# EthernetBridge.net
KiCad netlist of a schematic drawn in EAGLE
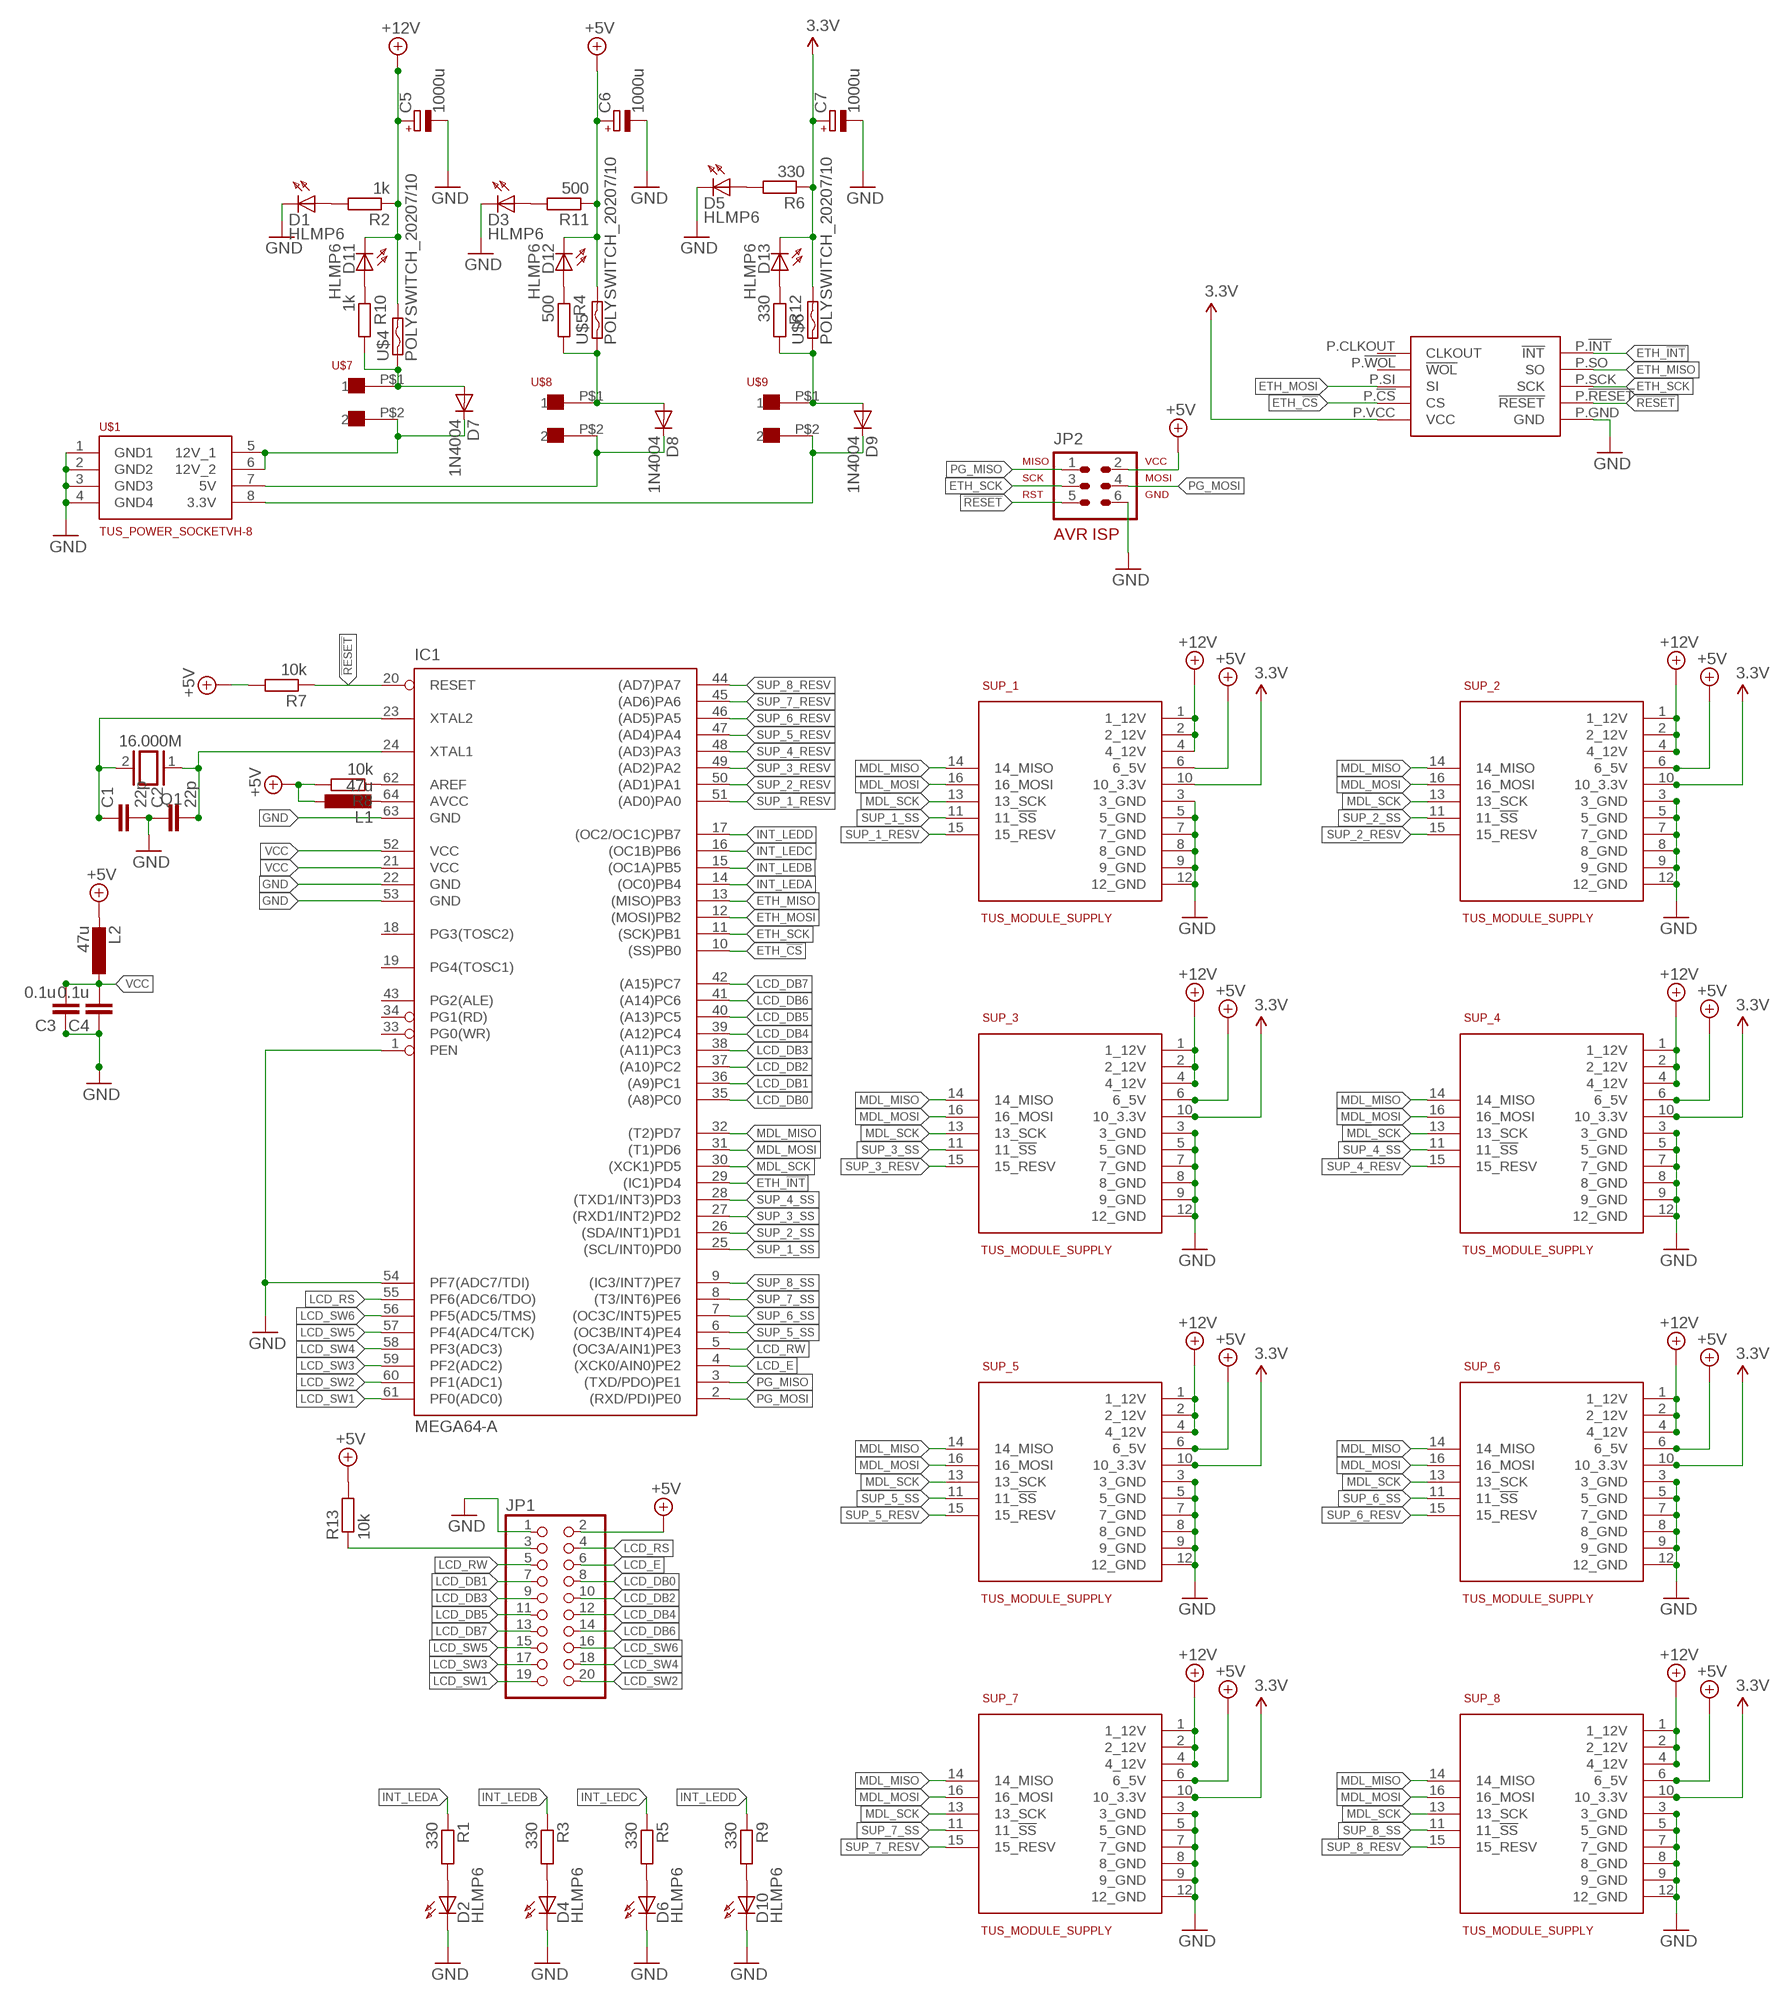
[diagram p0: schematic, sheet 1]

(export (version "E")
  (design (tool "Eeschema 10.0.6"))
  (components
    (comp (ref "C1")
      (value "22p")
      (footprint "eagle-import:C2.5-3")
      (libsource (lib "eagle-import") (part "C2,5-3"))
    )
    (comp (ref "C2")
      (value "22p")
      (footprint "eagle-import:C2.5-3")
      (libsource (lib "eagle-import") (part "C2,5-3"))
    )
    (comp (ref "C3")
      (value "0.1u")
      (footprint "eagle-import:C2.5-3")
      (libsource (lib "eagle-import") (part "C2,5-3"))
    )
    (comp (ref "C4")
      (value "0.1u")
      (footprint "eagle-import:C2.5-3")
      (libsource (lib "eagle-import") (part "C2,5-3"))
    )
    (comp (ref "C5")
      (value "1000u")
      (footprint "eagle-import:E5-10,5")
      (libsource (lib "eagle-import") (part "CPOL-EUE5-10.5"))
    )
    (comp (ref "C6")
      (value "1000u")
      (footprint "eagle-import:E5-10,5")
      (libsource (lib "eagle-import") (part "CPOL-EUE5-10.5"))
    )
    (comp (ref "C7")
      (value "1000u")
      (footprint "eagle-import:E5-10,5")
      (libsource (lib "eagle-import") (part "CPOL-EUE5-10.5"))
    )
    (comp (ref "D1")
      (value "HLMP6")
      (footprint "eagle-import:HLMP6")
      (fields (field (name "MF") "AGILENT TECHNOLOGIES") (field (name "MPN") "HLMP-6500"))
      (libsource (lib "eagle-import") (part "HLMP6"))
    )
    (comp (ref "D2")
      (value "HLMP6")
      (footprint "eagle-import:HLMP6")
      (fields (field (name "MF") "AGILENT TECHNOLOGIES") (field (name "MPN") "HLMP-6500"))
      (libsource (lib "eagle-import") (part "HLMP6"))
    )
    (comp (ref "D3")
      (value "HLMP6")
      (footprint "eagle-import:HLMP6")
      (fields (field (name "MF") "AGILENT TECHNOLOGIES") (field (name "MPN") "HLMP-6500"))
      (libsource (lib "eagle-import") (part "HLMP6"))
    )
    (comp (ref "D4")
      (value "HLMP6")
      (footprint "eagle-import:HLMP6")
      (fields (field (name "MF") "AGILENT TECHNOLOGIES") (field (name "MPN") "HLMP-6500"))
      (libsource (lib "eagle-import") (part "HLMP6"))
    )
    (comp (ref "D5")
      (value "HLMP6")
      (footprint "eagle-import:HLMP6")
      (fields (field (name "MF") "AGILENT TECHNOLOGIES") (field (name "MPN") "HLMP-6500"))
      (libsource (lib "eagle-import") (part "HLMP6"))
    )
    (comp (ref "D6")
      (value "HLMP6")
      (footprint "eagle-import:HLMP6")
      (fields (field (name "MF") "AGILENT TECHNOLOGIES") (field (name "MPN") "HLMP-6500"))
      (libsource (lib "eagle-import") (part "HLMP6"))
    )
    (comp (ref "D7")
      (value "1N4004")
      (footprint "eagle-import:DO41-10")
      (libsource (lib "eagle-import") (part "1N4004"))
    )
    (comp (ref "D8")
      (value "1N4004")
      (footprint "eagle-import:DO41-10")
      (libsource (lib "eagle-import") (part "1N4004"))
    )
    (comp (ref "D9")
      (value "1N4004")
      (footprint "eagle-import:DO41-10")
      (libsource (lib "eagle-import") (part "1N4004"))
    )
    (comp (ref "D10")
      (value "HLMP6")
      (footprint "eagle-import:HLMP6")
      (fields (field (name "MF") "AGILENT TECHNOLOGIES") (field (name "MPN") "HLMP-6500"))
      (libsource (lib "eagle-import") (part "HLMP6"))
    )
    (comp (ref "D11")
      (value "HLMP6")
      (footprint "eagle-import:HLMP6")
      (fields (field (name "MF") "AGILENT TECHNOLOGIES") (field (name "MPN") "HLMP-6500"))
      (libsource (lib "eagle-import") (part "HLMP6"))
    )
    (comp (ref "D12")
      (value "HLMP6")
      (footprint "eagle-import:HLMP6")
      (fields (field (name "MF") "AGILENT TECHNOLOGIES") (field (name "MPN") "HLMP-6500"))
      (libsource (lib "eagle-import") (part "HLMP6"))
    )
    (comp (ref "D13")
      (value "HLMP6")
      (footprint "eagle-import:HLMP6")
      (fields (field (name "MF") "AGILENT TECHNOLOGIES") (field (name "MPN") "HLMP-6500"))
      (libsource (lib "eagle-import") (part "HLMP6"))
    )
    (comp (ref "IC1")
      (value "MEGA64-A")
      (footprint "eagle-import:TQFP64")
      (fields (field (name "MPN") "ATMEGA64-16AU"))
      (libsource (lib "eagle-import") (part "MEGA64-A"))
    )
    (comp (ref "JP1")
      (value "PINHD-2X10")
      (footprint "eagle-import:2X10")
      (libsource (lib "eagle-import") (part "PINHD-2X10"))
    )
    (comp (ref "JP2")
      (value "AVR-ISP-6VERT")
      (footprint "eagle-import:AVR-ISP-6")
      (libsource (lib "eagle-import") (part "AVR-ISP-6VERT"))
    )
    (comp (ref "L1")
      (value "47u")
      (footprint "eagle-import:0204_7")
      (libsource (lib "eagle-import") (part "L-EU0204/7"))
    )
    (comp (ref "L2")
      (value "47u")
      (footprint "eagle-import:0204_7")
      (libsource (lib "eagle-import") (part "L-EU0204/7"))
    )
    (comp (ref "Q1")
      (value "16.000M")
      (footprint "eagle-import:QS")
      (libsource (lib "eagle-import") (part "XTAL/S"))
    )
    (comp (ref "R1")
      (value "330")
      (footprint "eagle-import:0204_7")
      (libsource (lib "eagle-import") (part "R-EU_0204/7"))
    )
    (comp (ref "R2")
      (value "1k")
      (footprint "eagle-import:0204_7")
      (libsource (lib "eagle-import") (part "R-EU_0204/7"))
    )
    (comp (ref "R3")
      (value "330")
      (footprint "eagle-import:0204_7")
      (libsource (lib "eagle-import") (part "R-EU_0204/7"))
    )
    (comp (ref "R4")
      (value "500")
      (footprint "eagle-import:0204_7")
      (libsource (lib "eagle-import") (part "R-EU_0204/7"))
    )
    (comp (ref "R5")
      (value "330")
      (footprint "eagle-import:0204_7")
      (libsource (lib "eagle-import") (part "R-EU_0204/7"))
    )
    (comp (ref "R6")
      (value "330")
      (footprint "eagle-import:0204_7")
      (libsource (lib "eagle-import") (part "R-EU_0204/7"))
    )
    (comp (ref "R7")
      (value "10k")
      (footprint "eagle-import:0204_7")
      (libsource (lib "eagle-import") (part "R-EU_0204/7"))
    )
    (comp (ref "R8")
      (value "10k")
      (footprint "eagle-import:0204_7")
      (libsource (lib "eagle-import") (part "R-EU_0204/7"))
    )
    (comp (ref "R9")
      (value "330")
      (footprint "eagle-import:0204_7")
      (libsource (lib "eagle-import") (part "R-EU_0204/7"))
    )
    (comp (ref "R10")
      (value "1k")
      (footprint "eagle-import:0204_7")
      (libsource (lib "eagle-import") (part "R-EU_0204/7"))
    )
    (comp (ref "R11")
      (value "500")
      (footprint "eagle-import:0204_7")
      (libsource (lib "eagle-import") (part "R-EU_0204/7"))
    )
    (comp (ref "R12")
      (value "330")
      (footprint "eagle-import:0204_7")
      (libsource (lib "eagle-import") (part "R-EU_0204/7"))
    )
    (comp (ref "R13")
      (value "10k")
      (footprint "eagle-import:0204_7")
      (libsource (lib "eagle-import") (part "R-EU_0204/7"))
    )
    (comp (ref "SUP_1")
      (value "TUS_MODULE_SUPPLY")
      (footprint "eagle-import:2X08")
      (libsource (lib "eagle-import") (part "TUS_MODULE_SUPPLY"))
    )
    (comp (ref "SUP_2")
      (value "TUS_MODULE_SUPPLY")
      (footprint "eagle-import:2X08")
      (libsource (lib "eagle-import") (part "TUS_MODULE_SUPPLY"))
    )
    (comp (ref "SUP_3")
      (value "TUS_MODULE_SUPPLY")
      (footprint "eagle-import:2X08")
      (libsource (lib "eagle-import") (part "TUS_MODULE_SUPPLY"))
    )
    (comp (ref "SUP_4")
      (value "TUS_MODULE_SUPPLY")
      (footprint "eagle-import:2X08")
      (libsource (lib "eagle-import") (part "TUS_MODULE_SUPPLY"))
    )
    (comp (ref "SUP_5")
      (value "TUS_MODULE_SUPPLY")
      (footprint "eagle-import:2X08")
      (libsource (lib "eagle-import") (part "TUS_MODULE_SUPPLY"))
    )
    (comp (ref "SUP_6")
      (value "TUS_MODULE_SUPPLY")
      (footprint "eagle-import:2X08")
      (libsource (lib "eagle-import") (part "TUS_MODULE_SUPPLY"))
    )
    (comp (ref "SUP_7")
      (value "TUS_MODULE_SUPPLY")
      (footprint "eagle-import:2X08")
      (libsource (lib "eagle-import") (part "TUS_MODULE_SUPPLY"))
    )
    (comp (ref "SUP_8")
      (value "TUS_MODULE_SUPPLY")
      (footprint "eagle-import:2X08")
      (libsource (lib "eagle-import") (part "TUS_MODULE_SUPPLY"))
    )
    (comp (ref "U$1")
      (value "TUS_POWER_SOCKETVH-8")
      (footprint "eagle-import:VH_8")
      (libsource (lib "eagle-import") (part "TUS_POWER_SOCKETVH-8"))
    )
    (comp (ref "U$2")
      (value "AITENDO_ENC28J60")
      (footprint "eagle-import:AITENDO_ENC28J60")
      (libsource (lib "eagle-import") (part "AITENDO_ENC28J60"))
    )
    (comp (ref "U$4")
      (value "POLYSWITCH_20207/10")
      (footprint "eagle-import:0207_10")
      (libsource (lib "eagle-import") (part "POLYSWITCH_20207/10"))
    )
    (comp (ref "U$5")
      (value "POLYSWITCH_20207/10")
      (footprint "eagle-import:0207_10")
      (libsource (lib "eagle-import") (part "POLYSWITCH_20207/10"))
    )
    (comp (ref "U$6")
      (value "POLYSWITCH_20207/10")
      (footprint "eagle-import:0207_10")
      (libsource (lib "eagle-import") (part "POLYSWITCH_20207/10"))
    )
    (comp (ref "U$7")
      (value "VH-2")
      (footprint "eagle-import:VH-2")
      (libsource (lib "eagle-import") (part "VH-2"))
    )
    (comp (ref "U$8")
      (value "VH-2")
      (footprint "eagle-import:VH-2")
      (libsource (lib "eagle-import") (part "VH-2"))
    )
    (comp (ref "U$9")
      (value "VH-2")
      (footprint "eagle-import:VH-2")
      (libsource (lib "eagle-import") (part "VH-2"))
    )
  )
  (nets
    (net (code "1") (name "+5V") (class "Default")
      (node (ref "C6") (pin "+") (pinfunction "+_+") (pintype "passive"))
      (node (ref "D12") (pin "K") (pinfunction "K_K") (pintype "passive"))
      (node (ref "JP1") (pin "2") (pinfunction "2_2") (pintype "passive"))
      (node (ref "JP2") (pin "2") (pinfunction "2_2") (pintype "passive"))
      (node (ref "L1") (pin "1") (pinfunction "1_1") (pintype "passive"))
      (node (ref "L2") (pin "2") (pinfunction "2_2") (pintype "passive"))
      (node (ref "R11") (pin "1") (pinfunction "1_1") (pintype "passive"))
      (node (ref "R13") (pin "2") (pinfunction "2_2") (pintype "passive"))
      (node (ref "R7") (pin "2") (pinfunction "2_2") (pintype "passive"))
      (node (ref "R8") (pin "2") (pinfunction "2_2") (pintype "passive"))
      (node (ref "SUP_1") (pin "6") (pinfunction "6_5V_6") (pintype "bidirectional"))
      (node (ref "SUP_2") (pin "6") (pinfunction "6_5V_6") (pintype "bidirectional"))
      (node (ref "SUP_3") (pin "6") (pinfunction "6_5V_6") (pintype "bidirectional"))
      (node (ref "SUP_4") (pin "6") (pinfunction "6_5V_6") (pintype "bidirectional"))
      (node (ref "SUP_5") (pin "6") (pinfunction "6_5V_6") (pintype "bidirectional"))
      (node (ref "SUP_6") (pin "6") (pinfunction "6_5V_6") (pintype "bidirectional"))
      (node (ref "SUP_7") (pin "6") (pinfunction "6_5V_6") (pintype "bidirectional"))
      (node (ref "SUP_8") (pin "6") (pinfunction "6_5V_6") (pintype "bidirectional"))
      (node (ref "U$5") (pin "2") (pinfunction "2_2") (pintype "passive"))
    )
    (net (code "2") (name "+12V") (class "Default")
      (node (ref "C5") (pin "+") (pinfunction "+_+") (pintype "passive"))
      (node (ref "D11") (pin "K") (pinfunction "K_K") (pintype "passive"))
      (node (ref "R2") (pin "1") (pinfunction "1_1") (pintype "passive"))
      (node (ref "SUP_1") (pin "1") (pinfunction "1_12V_1") (pintype "bidirectional"))
      (node (ref "SUP_1") (pin "2") (pinfunction "2_12V_2") (pintype "bidirectional"))
      (node (ref "SUP_1") (pin "4") (pinfunction "4_12V_4") (pintype "bidirectional"))
      (node (ref "SUP_2") (pin "1") (pinfunction "1_12V_1") (pintype "bidirectional"))
      (node (ref "SUP_2") (pin "2") (pinfunction "2_12V_2") (pintype "bidirectional"))
      (node (ref "SUP_2") (pin "4") (pinfunction "4_12V_4") (pintype "bidirectional"))
      (node (ref "SUP_3") (pin "1") (pinfunction "1_12V_1") (pintype "bidirectional"))
      (node (ref "SUP_3") (pin "2") (pinfunction "2_12V_2") (pintype "bidirectional"))
      (node (ref "SUP_3") (pin "4") (pinfunction "4_12V_4") (pintype "bidirectional"))
      (node (ref "SUP_4") (pin "1") (pinfunction "1_12V_1") (pintype "bidirectional"))
      (node (ref "SUP_4") (pin "2") (pinfunction "2_12V_2") (pintype "bidirectional"))
      (node (ref "SUP_4") (pin "4") (pinfunction "4_12V_4") (pintype "bidirectional"))
      (node (ref "SUP_5") (pin "1") (pinfunction "1_12V_1") (pintype "bidirectional"))
      (node (ref "SUP_5") (pin "2") (pinfunction "2_12V_2") (pintype "bidirectional"))
      (node (ref "SUP_5") (pin "4") (pinfunction "4_12V_4") (pintype "bidirectional"))
      (node (ref "SUP_6") (pin "1") (pinfunction "1_12V_1") (pintype "bidirectional"))
      (node (ref "SUP_6") (pin "2") (pinfunction "2_12V_2") (pintype "bidirectional"))
      (node (ref "SUP_6") (pin "4") (pinfunction "4_12V_4") (pintype "bidirectional"))
      (node (ref "SUP_7") (pin "1") (pinfunction "1_12V_1") (pintype "bidirectional"))
      (node (ref "SUP_7") (pin "2") (pinfunction "2_12V_2") (pintype "bidirectional"))
      (node (ref "SUP_7") (pin "4") (pinfunction "4_12V_4") (pintype "bidirectional"))
      (node (ref "SUP_8") (pin "1") (pinfunction "1_12V_1") (pintype "bidirectional"))
      (node (ref "SUP_8") (pin "2") (pinfunction "2_12V_2") (pintype "bidirectional"))
      (node (ref "SUP_8") (pin "4") (pinfunction "4_12V_4") (pintype "bidirectional"))
      (node (ref "U$4") (pin "2") (pinfunction "2_2") (pintype "passive"))
    )
    (net (code "3") (name "/ETH_~{CS}") (class "Default")
      (node (ref "IC1") (pin "10") (pinfunction "(SS)PB0_10") (pintype "bidirectional"))
      (node (ref "U$2") (pin "P.!CS") (pinfunction "CS_P.!CS") (pintype "bidirectional"))
    )
    (net (code "4") (name "/ETH_~{INT}") (class "Default")
      (node (ref "IC1") (pin "29") (pinfunction "(IC1)PD4_29") (pintype "bidirectional"))
      (node (ref "U$2") (pin "P.!INT") (pinfunction "~{INT}_P.!INT") (pintype "bidirectional"))
    )
    (net (code "5") (name "/~{RESET}") (class "Default")
      (node (ref "IC1") (pin "20") (pinfunction "RESET_20") (pintype "input"))
      (node (ref "JP2") (pin "5") (pinfunction "5_5") (pintype "passive"))
      (node (ref "R7") (pin "1") (pinfunction "1_1") (pintype "passive"))
      (node (ref "U$2") (pin "P.!RESET") (pinfunction "~{RESET}_P.!RESET") (pintype "bidirectional"))
    )
    (net (code "6") (name "3.3V") (class "Default")
      (node (ref "C7") (pin "+") (pinfunction "+_+") (pintype "passive"))
      (node (ref "D13") (pin "K") (pinfunction "K_K") (pintype "passive"))
      (node (ref "R6") (pin "1") (pinfunction "1_1") (pintype "passive"))
      (node (ref "SUP_1") (pin "10") (pinfunction "10_3.3V_10") (pintype "bidirectional"))
      (node (ref "SUP_2") (pin "10") (pinfunction "10_3.3V_10") (pintype "bidirectional"))
      (node (ref "SUP_3") (pin "10") (pinfunction "10_3.3V_10") (pintype "bidirectional"))
      (node (ref "SUP_4") (pin "10") (pinfunction "10_3.3V_10") (pintype "bidirectional"))
      (node (ref "SUP_5") (pin "10") (pinfunction "10_3.3V_10") (pintype "bidirectional"))
      (node (ref "SUP_6") (pin "10") (pinfunction "10_3.3V_10") (pintype "bidirectional"))
      (node (ref "SUP_7") (pin "10") (pinfunction "10_3.3V_10") (pintype "bidirectional"))
      (node (ref "SUP_8") (pin "10") (pinfunction "10_3.3V_10") (pintype "bidirectional"))
      (node (ref "U$2") (pin "P.VCC") (pinfunction "VCC_P.VCC") (pintype "bidirectional"))
      (node (ref "U$6") (pin "2") (pinfunction "2_2") (pintype "passive"))
    )
    (net (code "7") (name "ETH_MISO") (class "Default")
      (node (ref "IC1") (pin "13") (pinfunction "(MISO)PB3_13") (pintype "bidirectional"))
      (node (ref "U$2") (pin "P.SO") (pinfunction "SO_P.SO") (pintype "bidirectional"))
    )
    (net (code "8") (name "ETH_MOSI") (class "Default")
      (node (ref "IC1") (pin "12") (pinfunction "(MOSI)PB2_12") (pintype "bidirectional"))
      (node (ref "U$2") (pin "P.SI") (pinfunction "SI_P.SI") (pintype "bidirectional"))
    )
    (net (code "9") (name "ETH_SCK") (class "Default")
      (node (ref "IC1") (pin "11") (pinfunction "(SCK)PB1_11") (pintype "bidirectional"))
      (node (ref "JP2") (pin "3") (pinfunction "3_3") (pintype "passive"))
      (node (ref "U$2") (pin "P.SCK") (pinfunction "SCK_P.SCK") (pintype "bidirectional"))
    )
    (net (code "10") (name "GND") (class "Default")
      (node (ref "C1") (pin "2") (pinfunction "2_2") (pintype "passive"))
      (node (ref "C2") (pin "1") (pinfunction "1_1") (pintype "passive"))
      (node (ref "C3") (pin "1") (pinfunction "1_1") (pintype "passive"))
      (node (ref "C4") (pin "1") (pinfunction "1_1") (pintype "passive"))
      (node (ref "C5") (pin "-") (pinfunction "-_-") (pintype "passive"))
      (node (ref "C6") (pin "-") (pinfunction "-_-") (pintype "passive"))
      (node (ref "C7") (pin "-") (pinfunction "-_-") (pintype "passive"))
      (node (ref "D1") (pin "K") (pinfunction "K_K") (pintype "passive"))
      (node (ref "D10") (pin "K") (pinfunction "K_K") (pintype "passive"))
      (node (ref "D2") (pin "K") (pinfunction "K_K") (pintype "passive"))
      (node (ref "D3") (pin "K") (pinfunction "K_K") (pintype "passive"))
      (node (ref "D4") (pin "K") (pinfunction "K_K") (pintype "passive"))
      (node (ref "D5") (pin "K") (pinfunction "K_K") (pintype "passive"))
      (node (ref "D6") (pin "K") (pinfunction "K_K") (pintype "passive"))
      (node (ref "IC1") (pin "1") (pinfunction "PEN_1") (pintype "input"))
      (node (ref "IC1") (pin "22") (pinfunction "GND_22") (pintype "power_in"))
      (node (ref "IC1") (pin "53") (pinfunction "GND_53") (pintype "power_in"))
      (node (ref "IC1") (pin "54") (pinfunction "PF7(ADC7/TDI)_54") (pintype "input"))
      (node (ref "IC1") (pin "63") (pinfunction "GND_63") (pintype "power_in"))
      (node (ref "JP1") (pin "1") (pinfunction "1_1") (pintype "passive"))
      (node (ref "JP2") (pin "6") (pinfunction "6_6") (pintype "passive"))
      (node (ref "SUP_1") (pin "12") (pinfunction "12_GND_12") (pintype "bidirectional"))
      (node (ref "SUP_1") (pin "3") (pinfunction "3_GND_3") (pintype "bidirectional"))
      (node (ref "SUP_1") (pin "5") (pinfunction "5_GND_5") (pintype "bidirectional"))
      (node (ref "SUP_1") (pin "7") (pinfunction "7_GND_7") (pintype "bidirectional"))
      (node (ref "SUP_1") (pin "8") (pinfunction "8_GND_8") (pintype "bidirectional"))
      (node (ref "SUP_1") (pin "9") (pinfunction "9_GND_9") (pintype "bidirectional"))
      (node (ref "SUP_2") (pin "12") (pinfunction "12_GND_12") (pintype "bidirectional"))
      (node (ref "SUP_2") (pin "3") (pinfunction "3_GND_3") (pintype "bidirectional"))
      (node (ref "SUP_2") (pin "5") (pinfunction "5_GND_5") (pintype "bidirectional"))
      (node (ref "SUP_2") (pin "7") (pinfunction "7_GND_7") (pintype "bidirectional"))
      (node (ref "SUP_2") (pin "8") (pinfunction "8_GND_8") (pintype "bidirectional"))
      (node (ref "SUP_2") (pin "9") (pinfunction "9_GND_9") (pintype "bidirectional"))
      (node (ref "SUP_3") (pin "12") (pinfunction "12_GND_12") (pintype "bidirectional"))
      (node (ref "SUP_3") (pin "3") (pinfunction "3_GND_3") (pintype "bidirectional"))
      (node (ref "SUP_3") (pin "5") (pinfunction "5_GND_5") (pintype "bidirectional"))
      (node (ref "SUP_3") (pin "7") (pinfunction "7_GND_7") (pintype "bidirectional"))
      (node (ref "SUP_3") (pin "8") (pinfunction "8_GND_8") (pintype "bidirectional"))
      (node (ref "SUP_3") (pin "9") (pinfunction "9_GND_9") (pintype "bidirectional"))
      (node (ref "SUP_4") (pin "12") (pinfunction "12_GND_12") (pintype "bidirectional"))
      (node (ref "SUP_4") (pin "3") (pinfunction "3_GND_3") (pintype "bidirectional"))
      (node (ref "SUP_4") (pin "5") (pinfunction "5_GND_5") (pintype "bidirectional"))
      (node (ref "SUP_4") (pin "7") (pinfunction "7_GND_7") (pintype "bidirectional"))
      (node (ref "SUP_4") (pin "8") (pinfunction "8_GND_8") (pintype "bidirectional"))
      (node (ref "SUP_4") (pin "9") (pinfunction "9_GND_9") (pintype "bidirectional"))
      (node (ref "SUP_5") (pin "12") (pinfunction "12_GND_12") (pintype "bidirectional"))
      (node (ref "SUP_5") (pin "3") (pinfunction "3_GND_3") (pintype "bidirectional"))
      (node (ref "SUP_5") (pin "5") (pinfunction "5_GND_5") (pintype "bidirectional"))
      (node (ref "SUP_5") (pin "7") (pinfunction "7_GND_7") (pintype "bidirectional"))
      (node (ref "SUP_5") (pin "8") (pinfunction "8_GND_8") (pintype "bidirectional"))
      (node (ref "SUP_5") (pin "9") (pinfunction "9_GND_9") (pintype "bidirectional"))
      (node (ref "SUP_6") (pin "12") (pinfunction "12_GND_12") (pintype "bidirectional"))
      (node (ref "SUP_6") (pin "3") (pinfunction "3_GND_3") (pintype "bidirectional"))
      (node (ref "SUP_6") (pin "5") (pinfunction "5_GND_5") (pintype "bidirectional"))
      (node (ref "SUP_6") (pin "7") (pinfunction "7_GND_7") (pintype "bidirectional"))
      (node (ref "SUP_6") (pin "8") (pinfunction "8_GND_8") (pintype "bidirectional"))
      (node (ref "SUP_6") (pin "9") (pinfunction "9_GND_9") (pintype "bidirectional"))
      (node (ref "SUP_7") (pin "12") (pinfunction "12_GND_12") (pintype "bidirectional"))
      (node (ref "SUP_7") (pin "3") (pinfunction "3_GND_3") (pintype "bidirectional"))
      (node (ref "SUP_7") (pin "5") (pinfunction "5_GND_5") (pintype "bidirectional"))
      (node (ref "SUP_7") (pin "7") (pinfunction "7_GND_7") (pintype "bidirectional"))
      (node (ref "SUP_7") (pin "8") (pinfunction "8_GND_8") (pintype "bidirectional"))
      (node (ref "SUP_7") (pin "9") (pinfunction "9_GND_9") (pintype "bidirectional"))
      (node (ref "SUP_8") (pin "12") (pinfunction "12_GND_12") (pintype "bidirectional"))
      (node (ref "SUP_8") (pin "3") (pinfunction "3_GND_3") (pintype "bidirectional"))
      (node (ref "SUP_8") (pin "5") (pinfunction "5_GND_5") (pintype "bidirectional"))
      (node (ref "SUP_8") (pin "7") (pinfunction "7_GND_7") (pintype "bidirectional"))
      (node (ref "SUP_8") (pin "8") (pinfunction "8_GND_8") (pintype "bidirectional"))
      (node (ref "SUP_8") (pin "9") (pinfunction "9_GND_9") (pintype "bidirectional"))
      (node (ref "U$1") (pin "1") (pinfunction "GND1_1") (pintype "power_in"))
      (node (ref "U$1") (pin "2") (pinfunction "GND2_2") (pintype "power_in"))
      (node (ref "U$1") (pin "3") (pinfunction "GND3_3") (pintype "power_in"))
      (node (ref "U$1") (pin "4") (pinfunction "GND4_4") (pintype "power_in"))
      (node (ref "U$2") (pin "P.GND") (pinfunction "GND_P.GND") (pintype "bidirectional"))
    )
    (net (code "11") (name "INT_LEDA") (class "Default")
      (node (ref "IC1") (pin "14") (pinfunction "(OC0)PB4_14") (pintype "bidirectional"))
      (node (ref "R1") (pin "1") (pinfunction "1_1") (pintype "passive"))
    )
    (net (code "12") (name "INT_LEDB") (class "Default")
      (node (ref "IC1") (pin "15") (pinfunction "(OC1A)PB5_15") (pintype "bidirectional"))
      (node (ref "R3") (pin "1") (pinfunction "1_1") (pintype "passive"))
    )
    (net (code "13") (name "INT_LEDC") (class "Default")
      (node (ref "IC1") (pin "16") (pinfunction "(OC1B)PB6_16") (pintype "bidirectional"))
      (node (ref "R5") (pin "1") (pinfunction "1_1") (pintype "passive"))
    )
    (net (code "14") (name "INT_LEDD") (class "Default")
      (node (ref "IC1") (pin "17") (pinfunction "(OC2/OC1C)PB7_17") (pintype "bidirectional"))
      (node (ref "R9") (pin "1") (pinfunction "1_1") (pintype "passive"))
    )
    (net (code "15") (name "LCD_DB0") (class "Default")
      (node (ref "IC1") (pin "35") (pinfunction "(A8)PC0_35") (pintype "output"))
      (node (ref "JP1") (pin "8") (pinfunction "8_8") (pintype "passive"))
    )
    (net (code "16") (name "LCD_DB1") (class "Default")
      (node (ref "IC1") (pin "36") (pinfunction "(A9)PC1_36") (pintype "output"))
      (node (ref "JP1") (pin "7") (pinfunction "7_7") (pintype "passive"))
    )
    (net (code "17") (name "LCD_DB2") (class "Default")
      (node (ref "IC1") (pin "37") (pinfunction "(A10)PC2_37") (pintype "output"))
      (node (ref "JP1") (pin "10") (pinfunction "10_10") (pintype "passive"))
    )
    (net (code "18") (name "LCD_DB3") (class "Default")
      (node (ref "IC1") (pin "38") (pinfunction "(A11)PC3_38") (pintype "output"))
      (node (ref "JP1") (pin "9") (pinfunction "9_9") (pintype "passive"))
    )
    (net (code "19") (name "LCD_DB4") (class "Default")
      (node (ref "IC1") (pin "39") (pinfunction "(A12)PC4_39") (pintype "output"))
      (node (ref "JP1") (pin "12") (pinfunction "12_12") (pintype "passive"))
    )
    (net (code "20") (name "LCD_DB5") (class "Default")
      (node (ref "IC1") (pin "40") (pinfunction "(A13)PC5_40") (pintype "output"))
      (node (ref "JP1") (pin "11") (pinfunction "11_11") (pintype "passive"))
    )
    (net (code "21") (name "LCD_DB6") (class "Default")
      (node (ref "IC1") (pin "41") (pinfunction "(A14)PC6_41") (pintype "output"))
      (node (ref "JP1") (pin "14") (pinfunction "14_14") (pintype "passive"))
    )
    (net (code "22") (name "LCD_DB7") (class "Default")
      (node (ref "IC1") (pin "42") (pinfunction "(A15)PC7_42") (pintype "output"))
      (node (ref "JP1") (pin "13") (pinfunction "13_13") (pintype "passive"))
    )
    (net (code "23") (name "LCD_E") (class "Default")
      (node (ref "IC1") (pin "4") (pinfunction "(XCK0/AIN0)PE2_4") (pintype "bidirectional"))
      (node (ref "JP1") (pin "6") (pinfunction "6_6") (pintype "passive"))
    )
    (net (code "24") (name "LCD_RS") (class "Default")
      (node (ref "IC1") (pin "55") (pinfunction "PF6(ADC6/TDO)_55") (pintype "input"))
      (node (ref "JP1") (pin "4") (pinfunction "4_4") (pintype "passive"))
    )
    (net (code "25") (name "LCD_RW") (class "Default")
      (node (ref "IC1") (pin "5") (pinfunction "(OC3A/AIN1)PE3_5") (pintype "bidirectional"))
      (node (ref "JP1") (pin "5") (pinfunction "5_5") (pintype "passive"))
    )
    (net (code "26") (name "LCD_SW1") (class "Default")
      (node (ref "IC1") (pin "61") (pinfunction "PF0(ADC0)_61") (pintype "input"))
      (node (ref "JP1") (pin "19") (pinfunction "19_19") (pintype "passive"))
    )
    (net (code "27") (name "LCD_SW2") (class "Default")
      (node (ref "IC1") (pin "60") (pinfunction "PF1(ADC1)_60") (pintype "input"))
      (node (ref "JP1") (pin "20") (pinfunction "20_20") (pintype "passive"))
    )
    (net (code "28") (name "LCD_SW3") (class "Default")
      (node (ref "IC1") (pin "59") (pinfunction "PF2(ADC2)_59") (pintype "input"))
      (node (ref "JP1") (pin "17") (pinfunction "17_17") (pintype "passive"))
    )
    (net (code "29") (name "LCD_SW4") (class "Default")
      (node (ref "IC1") (pin "58") (pinfunction "PF3(ADC3)_58") (pintype "input"))
      (node (ref "JP1") (pin "18") (pinfunction "18_18") (pintype "passive"))
    )
    (net (code "30") (name "LCD_SW5") (class "Default")
      (node (ref "IC1") (pin "57") (pinfunction "PF4(ADC4/TCK)_57") (pintype "input"))
      (node (ref "JP1") (pin "15") (pinfunction "15_15") (pintype "passive"))
    )
    (net (code "31") (name "LCD_SW6") (class "Default")
      (node (ref "IC1") (pin "56") (pinfunction "PF5(ADC5/TMS)_56") (pintype "input"))
      (node (ref "JP1") (pin "16") (pinfunction "16_16") (pintype "passive"))
    )
    (net (code "32") (name "MDL_MISO") (class "Default")
      (node (ref "IC1") (pin "32") (pinfunction "(T2)PD7_32") (pintype "bidirectional"))
      (node (ref "SUP_1") (pin "14") (pinfunction "14_MISO_14") (pintype "bidirectional"))
      (node (ref "SUP_2") (pin "14") (pinfunction "14_MISO_14") (pintype "bidirectional"))
      (node (ref "SUP_3") (pin "14") (pinfunction "14_MISO_14") (pintype "bidirectional"))
      (node (ref "SUP_4") (pin "14") (pinfunction "14_MISO_14") (pintype "bidirectional"))
      (node (ref "SUP_5") (pin "14") (pinfunction "14_MISO_14") (pintype "bidirectional"))
      (node (ref "SUP_6") (pin "14") (pinfunction "14_MISO_14") (pintype "bidirectional"))
      (node (ref "SUP_7") (pin "14") (pinfunction "14_MISO_14") (pintype "bidirectional"))
      (node (ref "SUP_8") (pin "14") (pinfunction "14_MISO_14") (pintype "bidirectional"))
    )
    (net (code "33") (name "MDL_MOSI") (class "Default")
      (node (ref "IC1") (pin "31") (pinfunction "(T1)PD6_31") (pintype "bidirectional"))
      (node (ref "SUP_1") (pin "16") (pinfunction "16_MOSI_16") (pintype "bidirectional"))
      (node (ref "SUP_2") (pin "16") (pinfunction "16_MOSI_16") (pintype "bidirectional"))
      (node (ref "SUP_3") (pin "16") (pinfunction "16_MOSI_16") (pintype "bidirectional"))
      (node (ref "SUP_4") (pin "16") (pinfunction "16_MOSI_16") (pintype "bidirectional"))
      (node (ref "SUP_5") (pin "16") (pinfunction "16_MOSI_16") (pintype "bidirectional"))
      (node (ref "SUP_6") (pin "16") (pinfunction "16_MOSI_16") (pintype "bidirectional"))
      (node (ref "SUP_7") (pin "16") (pinfunction "16_MOSI_16") (pintype "bidirectional"))
      (node (ref "SUP_8") (pin "16") (pinfunction "16_MOSI_16") (pintype "bidirectional"))
    )
    (net (code "34") (name "MDL_SCK") (class "Default")
      (node (ref "IC1") (pin "30") (pinfunction "(XCK1)PD5_30") (pintype "bidirectional"))
      (node (ref "SUP_1") (pin "13") (pinfunction "13_SCK_13") (pintype "bidirectional"))
      (node (ref "SUP_2") (pin "13") (pinfunction "13_SCK_13") (pintype "bidirectional"))
      (node (ref "SUP_3") (pin "13") (pinfunction "13_SCK_13") (pintype "bidirectional"))
      (node (ref "SUP_4") (pin "13") (pinfunction "13_SCK_13") (pintype "bidirectional"))
      (node (ref "SUP_5") (pin "13") (pinfunction "13_SCK_13") (pintype "bidirectional"))
      (node (ref "SUP_6") (pin "13") (pinfunction "13_SCK_13") (pintype "bidirectional"))
      (node (ref "SUP_7") (pin "13") (pinfunction "13_SCK_13") (pintype "bidirectional"))
      (node (ref "SUP_8") (pin "13") (pinfunction "13_SCK_13") (pintype "bidirectional"))
    )
    (net (code "35") (name "Net-(D1-PadA)") (class "Default")
      (node (ref "D1") (pin "A") (pinfunction "A_A") (pintype "passive"))
      (node (ref "R2") (pin "2") (pinfunction "2_2") (pintype "passive"))
    )
    (net (code "36") (name "Net-(D2-PadA)") (class "Default")
      (node (ref "D2") (pin "A") (pinfunction "A_A") (pintype "passive"))
      (node (ref "R1") (pin "2") (pinfunction "2_2") (pintype "passive"))
    )
    (net (code "37") (name "Net-(D3-PadA)") (class "Default")
      (node (ref "D3") (pin "A") (pinfunction "A_A") (pintype "passive"))
      (node (ref "R11") (pin "2") (pinfunction "2_2") (pintype "passive"))
    )
    (net (code "38") (name "Net-(D4-PadA)") (class "Default")
      (node (ref "D4") (pin "A") (pinfunction "A_A") (pintype "passive"))
      (node (ref "R3") (pin "2") (pinfunction "2_2") (pintype "passive"))
    )
    (net (code "39") (name "Net-(D5-PadA)") (class "Default")
      (node (ref "D5") (pin "A") (pinfunction "A_A") (pintype "passive"))
      (node (ref "R6") (pin "2") (pinfunction "2_2") (pintype "passive"))
    )
    (net (code "40") (name "Net-(D6-PadA)") (class "Default")
      (node (ref "D6") (pin "A") (pinfunction "A_A") (pintype "passive"))
      (node (ref "R5") (pin "2") (pinfunction "2_2") (pintype "passive"))
    )
    (net (code "41") (name "Net-(D10-PadA)") (class "Default")
      (node (ref "D10") (pin "A") (pinfunction "A_A") (pintype "passive"))
      (node (ref "R9") (pin "2") (pinfunction "2_2") (pintype "passive"))
    )
    (net (code "42") (name "Net-(D11-PadA)") (class "Default")
      (node (ref "D11") (pin "A") (pinfunction "A_A") (pintype "passive"))
      (node (ref "R10") (pin "1") (pinfunction "1_1") (pintype "passive"))
    )
    (net (code "43") (name "Net-(D12-PadA)") (class "Default")
      (node (ref "D12") (pin "A") (pinfunction "A_A") (pintype "passive"))
      (node (ref "R4") (pin "1") (pinfunction "1_1") (pintype "passive"))
    )
    (net (code "44") (name "Net-(D13-PadA)") (class "Default")
      (node (ref "D13") (pin "A") (pinfunction "A_A") (pintype "passive"))
      (node (ref "R12") (pin "1") (pinfunction "1_1") (pintype "passive"))
    )
    (net (code "45") (name "Net-(IC1-AREF)") (class "Default")
      (node (ref "IC1") (pin "62") (pinfunction "AREF_62") (pintype "passive"))
      (node (ref "R8") (pin "1") (pinfunction "1_1") (pintype "passive"))
    )
    (net (code "46") (name "Net-(IC1-AVCC)") (class "Default")
      (node (ref "IC1") (pin "64") (pinfunction "AVCC_64") (pintype "power_in"))
      (node (ref "L1") (pin "2") (pinfunction "2_2") (pintype "passive"))
    )
    (net (code "47") (name "Net-(IC1-XTAL1)") (class "Default")
      (node (ref "C2") (pin "2") (pinfunction "2_2") (pintype "passive"))
      (node (ref "IC1") (pin "24") (pinfunction "XTAL1_24") (pintype "bidirectional"))
      (node (ref "Q1") (pin "1") (pinfunction "1_1") (pintype "passive"))
    )
    (net (code "48") (name "Net-(IC1-XTAL2)") (class "Default")
      (node (ref "C1") (pin "1") (pinfunction "1_1") (pintype "passive"))
      (node (ref "IC1") (pin "23") (pinfunction "XTAL2_23") (pintype "bidirectional"))
      (node (ref "Q1") (pin "2") (pinfunction "2_2") (pintype "passive"))
    )
    (net (code "49") (name "Net-(JP1-Pad3)") (class "Default")
      (node (ref "JP1") (pin "3") (pinfunction "3_3") (pintype "passive"))
      (node (ref "R13") (pin "1") (pinfunction "1_1") (pintype "passive"))
    )
    (net (code "50") (name "Net-(U$1-3.3V)") (class "Default")
      (node (ref "D9") (pin "C") (pinfunction "C_C") (pintype "passive"))
      (node (ref "U$1") (pin "8") (pinfunction "3.3V_8") (pintype "power_in"))
      (node (ref "U$9") (pin "P$2") (pinfunction "2_P$2") (pintype "bidirectional"))
    )
    (net (code "51") (name "Net-(U$1-5V)") (class "Default")
      (node (ref "D8") (pin "C") (pinfunction "C_C") (pintype "passive"))
      (node (ref "U$1") (pin "7") (pinfunction "5V_7") (pintype "power_in"))
      (node (ref "U$8") (pin "P$2") (pinfunction "2_P$2") (pintype "bidirectional"))
    )
    (net (code "52") (name "Net-(U$1-12V_1)") (class "Default")
      (node (ref "D7") (pin "C") (pinfunction "C_C") (pintype "passive"))
      (node (ref "U$1") (pin "5") (pinfunction "12V_1_5") (pintype "power_in"))
      (node (ref "U$1") (pin "6") (pinfunction "12V_2_6") (pintype "power_in"))
      (node (ref "U$7") (pin "P$2") (pinfunction "2_P$2") (pintype "bidirectional"))
    )
    (net (code "53") (name "Net-(U$7-1)") (class "Default")
      (node (ref "D7") (pin "A") (pinfunction "A_A") (pintype "passive"))
      (node (ref "R10") (pin "2") (pinfunction "2_2") (pintype "passive"))
      (node (ref "U$4") (pin "1") (pinfunction "1_1") (pintype "passive"))
      (node (ref "U$7") (pin "P$1") (pinfunction "1_P$1") (pintype "bidirectional"))
    )
    (net (code "54") (name "Net-(U$8-1)") (class "Default")
      (node (ref "D8") (pin "A") (pinfunction "A_A") (pintype "passive"))
      (node (ref "R4") (pin "2") (pinfunction "2_2") (pintype "passive"))
      (node (ref "U$5") (pin "1") (pinfunction "1_1") (pintype "passive"))
      (node (ref "U$8") (pin "P$1") (pinfunction "1_P$1") (pintype "bidirectional"))
    )
    (net (code "55") (name "Net-(U$9-1)") (class "Default")
      (node (ref "D9") (pin "A") (pinfunction "A_A") (pintype "passive"))
      (node (ref "R12") (pin "2") (pinfunction "2_2") (pintype "passive"))
      (node (ref "U$6") (pin "1") (pinfunction "1_1") (pintype "passive"))
      (node (ref "U$9") (pin "P$1") (pinfunction "1_P$1") (pintype "bidirectional"))
    )
    (net (code "56") (name "PG_MISO") (class "Default")
      (node (ref "IC1") (pin "3") (pinfunction "(TXD/PDO)PE1_3") (pintype "bidirectional"))
      (node (ref "JP2") (pin "1") (pinfunction "1_1") (pintype "passive"))
    )
    (net (code "57") (name "PG_MOSI") (class "Default")
      (node (ref "IC1") (pin "2") (pinfunction "(RXD/PDI)PE0_2") (pintype "bidirectional"))
      (node (ref "JP2") (pin "4") (pinfunction "4_4") (pintype "passive"))
    )
    (net (code "58") (name "SUP_1_RESV") (class "Default")
      (node (ref "IC1") (pin "51") (pinfunction "(AD0)PA0_51") (pintype "bidirectional"))
      (node (ref "SUP_1") (pin "15") (pinfunction "15_RESV_15") (pintype "bidirectional"))
    )
    (net (code "59") (name "SUP_1_SS") (class "Default")
      (node (ref "IC1") (pin "25") (pinfunction "(SCL/INT0)PD0_25") (pintype "bidirectional"))
      (node (ref "SUP_1") (pin "11") (pinfunction "11_~{SS}_11") (pintype "bidirectional"))
    )
    (net (code "60") (name "SUP_2_RESV") (class "Default")
      (node (ref "IC1") (pin "50") (pinfunction "(AD1)PA1_50") (pintype "bidirectional"))
      (node (ref "SUP_2") (pin "15") (pinfunction "15_RESV_15") (pintype "bidirectional"))
    )
    (net (code "61") (name "SUP_2_SS") (class "Default")
      (node (ref "IC1") (pin "26") (pinfunction "(SDA/INT1)PD1_26") (pintype "bidirectional"))
      (node (ref "SUP_2") (pin "11") (pinfunction "11_~{SS}_11") (pintype "bidirectional"))
    )
    (net (code "62") (name "SUP_3_RESV") (class "Default")
      (node (ref "IC1") (pin "49") (pinfunction "(AD2)PA2_49") (pintype "bidirectional"))
      (node (ref "SUP_3") (pin "15") (pinfunction "15_RESV_15") (pintype "bidirectional"))
    )
    (net (code "63") (name "SUP_3_SS") (class "Default")
      (node (ref "IC1") (pin "27") (pinfunction "(RXD1/INT2)PD2_27") (pintype "bidirectional"))
      (node (ref "SUP_3") (pin "11") (pinfunction "11_~{SS}_11") (pintype "bidirectional"))
    )
    (net (code "64") (name "SUP_4_RESV") (class "Default")
      (node (ref "IC1") (pin "48") (pinfunction "(AD3)PA3_48") (pintype "bidirectional"))
      (node (ref "SUP_4") (pin "15") (pinfunction "15_RESV_15") (pintype "bidirectional"))
    )
    (net (code "65") (name "SUP_4_SS") (class "Default")
      (node (ref "IC1") (pin "28") (pinfunction "(TXD1/INT3)PD3_28") (pintype "bidirectional"))
      (node (ref "SUP_4") (pin "11") (pinfunction "11_~{SS}_11") (pintype "bidirectional"))
    )
    (net (code "66") (name "SUP_5_RESV") (class "Default")
      (node (ref "IC1") (pin "47") (pinfunction "(AD4)PA4_47") (pintype "bidirectional"))
      (node (ref "SUP_5") (pin "15") (pinfunction "15_RESV_15") (pintype "bidirectional"))
    )
    (net (code "67") (name "SUP_5_SS") (class "Default")
      (node (ref "IC1") (pin "6") (pinfunction "(OC3B/INT4)PE4_6") (pintype "bidirectional"))
      (node (ref "SUP_5") (pin "11") (pinfunction "11_~{SS}_11") (pintype "bidirectional"))
    )
    (net (code "68") (name "SUP_6_RESV") (class "Default")
      (node (ref "IC1") (pin "46") (pinfunction "(AD5)PA5_46") (pintype "bidirectional"))
      (node (ref "SUP_6") (pin "15") (pinfunction "15_RESV_15") (pintype "bidirectional"))
    )
    (net (code "69") (name "SUP_6_SS") (class "Default")
      (node (ref "IC1") (pin "7") (pinfunction "(OC3C/INT5)PE5_7") (pintype "bidirectional"))
      (node (ref "SUP_6") (pin "11") (pinfunction "11_~{SS}_11") (pintype "bidirectional"))
    )
    (net (code "70") (name "SUP_7_RESV") (class "Default")
      (node (ref "IC1") (pin "45") (pinfunction "(AD6)PA6_45") (pintype "bidirectional"))
      (node (ref "SUP_7") (pin "15") (pinfunction "15_RESV_15") (pintype "bidirectional"))
    )
    (net (code "71") (name "SUP_7_SS") (class "Default")
      (node (ref "IC1") (pin "8") (pinfunction "(T3/INT6)PE6_8") (pintype "bidirectional"))
      (node (ref "SUP_7") (pin "11") (pinfunction "11_~{SS}_11") (pintype "bidirectional"))
    )
    (net (code "72") (name "SUP_8_RESV") (class "Default")
      (node (ref "IC1") (pin "44") (pinfunction "(AD7)PA7_44") (pintype "bidirectional"))
      (node (ref "SUP_8") (pin "15") (pinfunction "15_RESV_15") (pintype "bidirectional"))
    )
    (net (code "73") (name "SUP_8_SS") (class "Default")
      (node (ref "IC1") (pin "9") (pinfunction "(IC3/INT7)PE7_9") (pintype "bidirectional"))
      (node (ref "SUP_8") (pin "11") (pinfunction "11_~{SS}_11") (pintype "bidirectional"))
    )
    (net (code "74") (name "VCC") (class "Default")
      (node (ref "C3") (pin "2") (pinfunction "2_2") (pintype "passive"))
      (node (ref "C4") (pin "2") (pinfunction "2_2") (pintype "passive"))
      (node (ref "IC1") (pin "21") (pinfunction "VCC_21") (pintype "power_in"))
      (node (ref "IC1") (pin "52") (pinfunction "VCC_52") (pintype "power_in"))
      (node (ref "L2") (pin "1") (pinfunction "1_1") (pintype "passive"))
    )
    (net (code "75") (name "unconnected-(IC1-PG0(WR)-Pad33)") (class "Default")
      (node (ref "IC1") (pin "33") (pinfunction "PG0(WR)_33") (pintype "bidirectional"))
    )
    (net (code "76") (name "unconnected-(IC1-PG1(RD)-Pad34)") (class "Default")
      (node (ref "IC1") (pin "34") (pinfunction "PG1(RD)_34") (pintype "bidirectional"))
    )
    (net (code "77") (name "unconnected-(IC1-PG2(ALE)-Pad43)") (class "Default")
      (node (ref "IC1") (pin "43") (pinfunction "PG2(ALE)_43") (pintype "bidirectional"))
    )
    (net (code "78") (name "unconnected-(IC1-PG3(TOSC2)-Pad18)") (class "Default")
      (node (ref "IC1") (pin "18") (pinfunction "PG3(TOSC2)_18") (pintype "bidirectional"))
    )
    (net (code "79") (name "unconnected-(IC1-PG4(TOSC1)-Pad19)") (class "Default")
      (node (ref "IC1") (pin "19") (pinfunction "PG4(TOSC1)_19") (pintype "bidirectional"))
    )
    (net (code "80") (name "unconnected-(U$2-CLKOUT-PadP.CLKOUT)") (class "Default")
      (node (ref "U$2") (pin "P.CLKOUT") (pinfunction "CLKOUT_P.CLKOUT") (pintype "bidirectional"))
    )
    (net (code "81") (name "unconnected-(U$2-~{WOL}-PadP.!WOL)") (class "Default")
      (node (ref "U$2") (pin "P.!WOL") (pinfunction "~{WOL}_P.!WOL") (pintype "bidirectional"))
    )
  )
)
